# 3V3_Regulator.net
KiCad netlist of a schematic drawn in Altium Designer
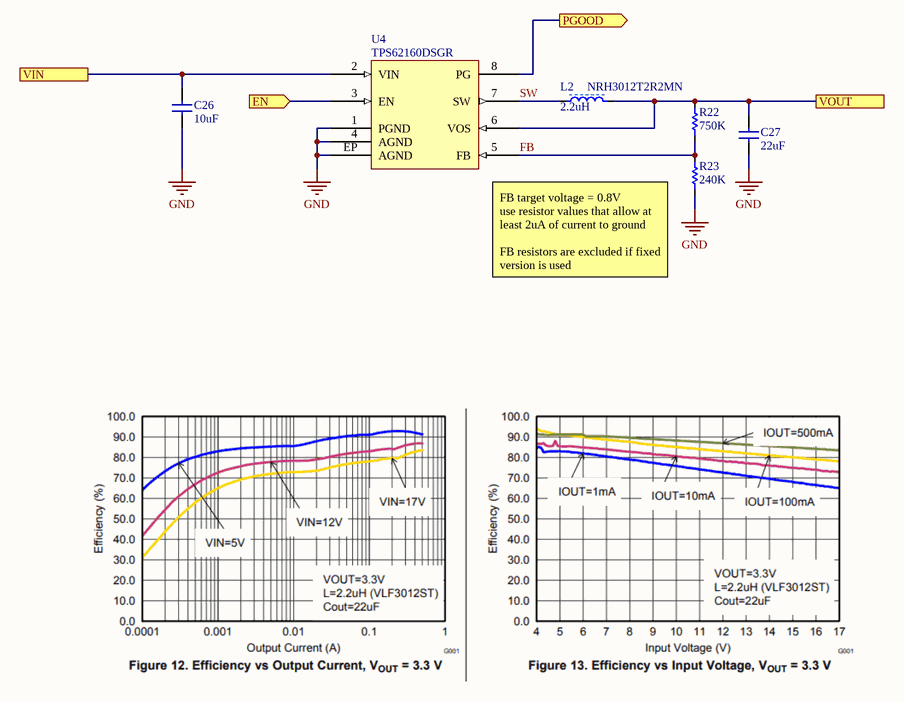
[diagram p0: 3V3_Regulator.SchDoc]

(export (version "E")
  (design (tool "Eeschema 10.0.6"))
  (components
    (comp (ref "C26")
      (value "10uF")
      (footprint "0805_Capacitor")
      (description "CAP CER 10UF 25V X5R 0805")
      (fields (field (name "VOLTAGE") "25V") (field (name "Comment") "CAP 10uF 25V X5R"))
      (libsource (lib "capacitor") (part "C_0805_10uF_25V_10%"))
    )
    (comp (ref "C27")
      (value "22uF")
      (footprint "0805_Capacitor")
      (description "CAP CERM 22uF 20% 16V 0805")
      (fields (field (name "VOLTAGE") "16V") (field (name "Comment") "CAP 22uF 16V X5R"))
      (libsource (lib "capacitor") (part "C_0805_22uF_16V_20%"))
    )
    (comp (ref "L2")
      (value "NRH3012T2R2MN")
      (footprint "L_NR_Series_3.0x3.0mm")
      (description "2.2µH Shielded Wirewound Inductor 1.37A 90mOhm Max Nonstandard")
      (fields
        (field (name "TOLERANCE") "20%")
        (field (name "MANUFACTURER") "Taiyo Yuden")
        (field (name "ALTIUM_VALUE") "2.2uH")
      )
      (libsource (lib "inductor") (part "L_NRH3012T2R2MN"))
    )
    (comp (ref "R22")
      (value "750K")
      (footprint "0402_Resistor")
      (description "Generic 0402 Resistor (10.2R to 10M)")
      (fields (field (name "TOLERANCE") "±1%") (field (name "MANUFACTURER") "Yageo"))
      (libsource (lib "resistor") (part "R_0402_generic_1%"))
    )
    (comp (ref "R23")
      (value "240K")
      (footprint "0402_Resistor")
      (description "Generic 0402 Resistor (10.2R to 10M)")
      (fields (field (name "TOLERANCE") "±1%") (field (name "MANUFACTURER") "Yageo"))
      (libsource (lib "resistor") (part "R_0402_generic_1%"))
    )
    (comp (ref "U4")
      (value "TPS62160DSGR")
      (footprint "WFDFN-8-EP")
      (description "Buck Switching Regulator IC Positive Adjustable 0.9V 1 Output 1A")
      (libsource (lib "ic") (part "U_TPS62160"))
    )
  )
  (nets
    (net (code "1") (name "/EN") (class "Default")
      (node (ref "U4") (pin "3") (pinfunction "EN_3") (pintype "input"))
    )
    (net (code "2") (name "/FB") (class "Default")
      (node (ref "R22") (pin "1") (pinfunction "1_1") (pintype "passive"))
      (node (ref "R23") (pin "2") (pinfunction "2_2") (pintype "passive"))
      (node (ref "U4") (pin "5") (pinfunction "FB_5") (pintype "input"))
    )
    (net (code "3") (name "/PGOOD") (class "Default")
      (node (ref "U4") (pin "8") (pinfunction "PG_8") (pintype "open_collector"))
    )
    (net (code "4") (name "/SW") (class "Default")
      (node (ref "L2") (pin "1") (pinfunction "1_1") (pintype "passive"))
      (node (ref "U4") (pin "7") (pinfunction "SW_7") (pintype "output"))
    )
    (net (code "5") (name "/VIN") (class "Default")
      (node (ref "C26") (pin "1") (pinfunction "1_1") (pintype "passive"))
      (node (ref "U4") (pin "2") (pinfunction "VIN_2") (pintype "input"))
    )
    (net (code "6") (name "/VOUT") (class "Default")
      (node (ref "C27") (pin "1") (pinfunction "1_1") (pintype "passive"))
      (node (ref "L2") (pin "2") (pinfunction "2_2") (pintype "passive"))
      (node (ref "R22") (pin "2") (pinfunction "2_2") (pintype "passive"))
      (node (ref "U4") (pin "6") (pinfunction "VOS_6") (pintype "input"))
    )
    (net (code "7") (name "GND") (class "Default")
      (node (ref "C26") (pin "2") (pinfunction "2_2") (pintype "passive"))
      (node (ref "C27") (pin "2") (pinfunction "2_2") (pintype "passive"))
      (node (ref "R23") (pin "1") (pinfunction "1_1") (pintype "passive"))
      (node (ref "U4") (pin "1") (pinfunction "PGND_1") (pintype "power_in"))
      (node (ref "U4") (pin "4") (pinfunction "AGND_4") (pintype "power_in"))
      (node (ref "U4") (pin "EP") (pinfunction "AGND_EP") (pintype "power_in"))
    )
  )
)
